# Overgang.net
KiCad netlist of a schematic drawn in EAGLE
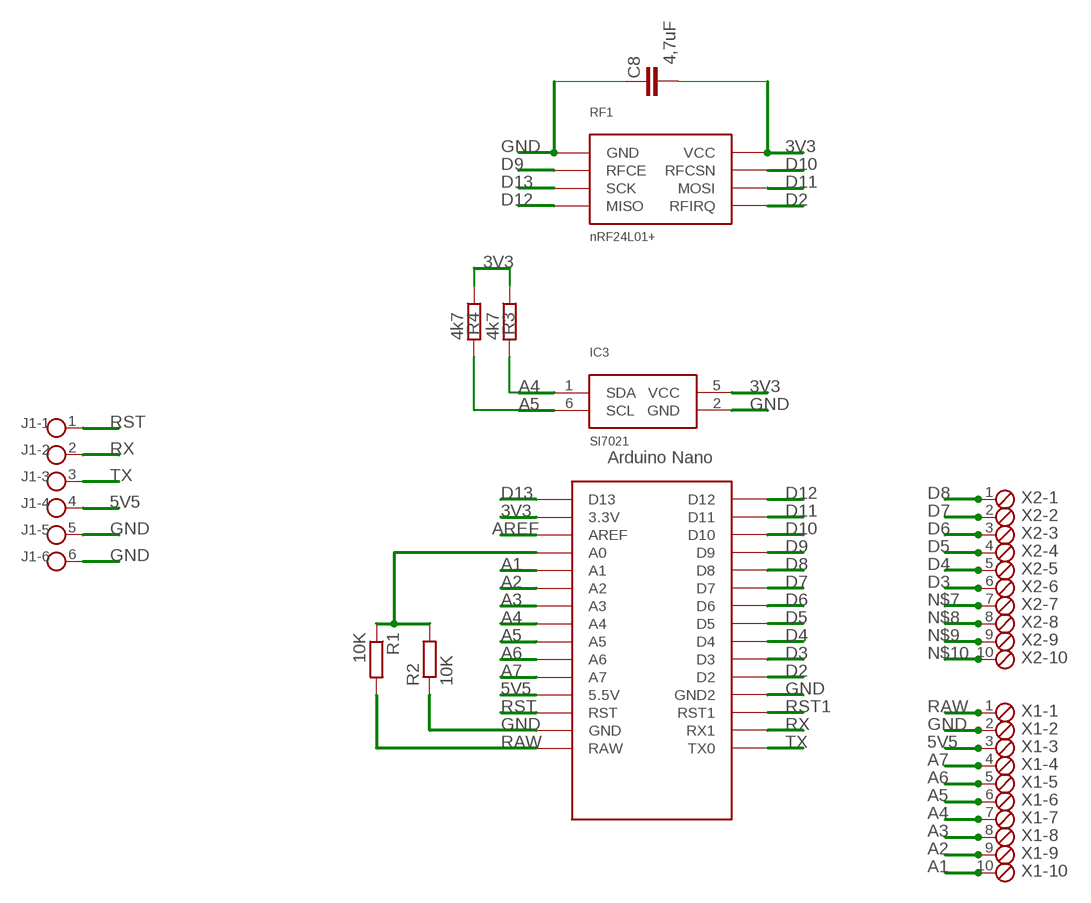
[diagram p0: schematic, sheet 1]

(export (version "E")
  (design (tool "Eeschema 10.0.6"))
  (components
    (comp (ref "C8")
      (value "4,7uF")
      (footprint "eagle-import:C1206K")
      (libsource (lib "eagle-import") (part "C-EUC1206K"))
    )
    (comp (ref "IC3")
      (value "SI7021")
      (footprint "eagle-import:DFN6")
      (libsource (lib "eagle-import") (part "SI7021"))
    )
    (comp (ref "J1")
      (value "FTDI")
      (footprint "eagle-import:LIST6B")
      (libsource (lib "eagle-import") (part "LIST6LIST6B"))
    )
    (comp (ref "R1")
      (value "10K")
      (footprint "eagle-import:R0805")
      (libsource (lib "eagle-import") (part "R-EU_R0805"))
    )
    (comp (ref "R2")
      (value "10K")
      (footprint "eagle-import:R0805")
      (libsource (lib "eagle-import") (part "R-EU_R0805"))
    )
    (comp (ref "R3")
      (value "4k7")
      (footprint "eagle-import:R0805")
      (libsource (lib "eagle-import") (part "R-EU_R0805"))
    )
    (comp (ref "R4")
      (value "4k7")
      (footprint "eagle-import:R0805")
      (libsource (lib "eagle-import") (part "R-EU_R0805"))
    )
    (comp (ref "RF1")
      (value "nRF24L01+")
      (footprint "eagle-import:2X4-2.54MM")
      (libsource (lib "eagle-import") (part "NRF24L01"))
    )
    (comp (ref "U$1")
      (value "NANO")
      (footprint "eagle-import:NANO")
      (libsource (lib "eagle-import") (part "NANO"))
    )
    (comp (ref "X1")
      (value "MPT10")
      (footprint "eagle-import:10POL254")
      (libsource (lib "eagle-import") (part "MPT10"))
    )
    (comp (ref "X2")
      (value "MPT10")
      (footprint "eagle-import:10POL254")
      (libsource (lib "eagle-import") (part "MPT10"))
    )
  )
  (nets
    (net (code "1") (name "/3V3") (class "Default")
      (node (ref "C8") (pin "1") (pinfunction "1_1") (pintype "passive"))
      (node (ref "IC3") (pin "5") (pinfunction "VCC_5") (pintype "bidirectional"))
      (node (ref "R3") (pin "1") (pinfunction "1_1") (pintype "passive"))
      (node (ref "R4") (pin "1") (pinfunction "1_1") (pintype "passive"))
      (node (ref "RF1") (pin "P$2") (pinfunction "VCC_P$2") (pintype "power_in"))
      (node (ref "U$1") (pin "3.3V") (pinfunction "3.3V_3.3V") (pintype "bidirectional"))
    )
    (net (code "2") (name "/5V5") (class "Default")
      (node (ref "J1") (pin "4") (pinfunction "1_4") (pintype "passive"))
      (node (ref "U$1") (pin "5V") (pinfunction "5.5V_5V") (pintype "bidirectional"))
      (node (ref "X1") (pin "3") (pinfunction "1_3") (pintype "passive"))
    )
    (net (code "3") (name "/A1") (class "Default")
      (node (ref "U$1") (pin "A1") (pinfunction "A1_A1") (pintype "bidirectional"))
      (node (ref "X1") (pin "10") (pinfunction "1_10") (pintype "passive"))
    )
    (net (code "4") (name "/A2") (class "Default")
      (node (ref "U$1") (pin "A2") (pinfunction "A2_A2") (pintype "bidirectional"))
      (node (ref "X1") (pin "9") (pinfunction "1_9") (pintype "passive"))
    )
    (net (code "5") (name "/A3") (class "Default")
      (node (ref "U$1") (pin "A3") (pinfunction "A3_A3") (pintype "bidirectional"))
      (node (ref "X1") (pin "8") (pinfunction "1_8") (pintype "passive"))
    )
    (net (code "6") (name "/A4") (class "Default")
      (node (ref "IC3") (pin "1") (pinfunction "SDA_1") (pintype "bidirectional"))
      (node (ref "R3") (pin "2") (pinfunction "2_2") (pintype "passive"))
      (node (ref "U$1") (pin "A4") (pinfunction "A4_A4") (pintype "bidirectional"))
      (node (ref "X1") (pin "7") (pinfunction "1_7") (pintype "passive"))
    )
    (net (code "7") (name "/A5") (class "Default")
      (node (ref "IC3") (pin "6") (pinfunction "SCL_6") (pintype "bidirectional"))
      (node (ref "R4") (pin "2") (pinfunction "2_2") (pintype "passive"))
      (node (ref "U$1") (pin "A5") (pinfunction "A5_A5") (pintype "bidirectional"))
      (node (ref "X1") (pin "6") (pinfunction "1_6") (pintype "passive"))
    )
    (net (code "8") (name "/A6") (class "Default")
      (node (ref "U$1") (pin "A6") (pinfunction "A6_A6") (pintype "bidirectional"))
      (node (ref "X1") (pin "5") (pinfunction "1_5") (pintype "passive"))
    )
    (net (code "9") (name "/A7") (class "Default")
      (node (ref "U$1") (pin "A7") (pinfunction "A7_A7") (pintype "bidirectional"))
      (node (ref "X1") (pin "4") (pinfunction "1_4") (pintype "passive"))
    )
    (net (code "10") (name "/AREF") (class "Default")
      (node (ref "U$1") (pin "AREF") (pinfunction "AREF_AREF") (pintype "bidirectional"))
    )
    (net (code "11") (name "/D2") (class "Default")
      (node (ref "RF1") (pin "P$8") (pinfunction "RFIRQ_P$8") (pintype "output"))
      (node (ref "U$1") (pin "D2") (pinfunction "D2_D2") (pintype "bidirectional"))
    )
    (net (code "12") (name "/D3") (class "Default")
      (node (ref "U$1") (pin "D3") (pinfunction "D3_D3") (pintype "bidirectional"))
      (node (ref "X2") (pin "6") (pinfunction "1_6") (pintype "passive"))
    )
    (net (code "13") (name "/D4") (class "Default")
      (node (ref "U$1") (pin "D4") (pinfunction "D4_D4") (pintype "bidirectional"))
      (node (ref "X2") (pin "5") (pinfunction "1_5") (pintype "passive"))
    )
    (net (code "14") (name "/D5") (class "Default")
      (node (ref "U$1") (pin "D5") (pinfunction "D5_D5") (pintype "bidirectional"))
      (node (ref "X2") (pin "4") (pinfunction "1_4") (pintype "passive"))
    )
    (net (code "15") (name "/D6") (class "Default")
      (node (ref "U$1") (pin "D6") (pinfunction "D6_D6") (pintype "bidirectional"))
      (node (ref "X2") (pin "3") (pinfunction "1_3") (pintype "passive"))
    )
    (net (code "16") (name "/D7") (class "Default")
      (node (ref "U$1") (pin "D7") (pinfunction "D7_D7") (pintype "bidirectional"))
      (node (ref "X2") (pin "2") (pinfunction "1_2") (pintype "passive"))
    )
    (net (code "17") (name "/D8") (class "Default")
      (node (ref "U$1") (pin "D8") (pinfunction "D8_D8") (pintype "bidirectional"))
      (node (ref "X2") (pin "1") (pinfunction "1_1") (pintype "passive"))
    )
    (net (code "18") (name "/D9") (class "Default")
      (node (ref "RF1") (pin "P$3") (pinfunction "RFCE_P$3") (pintype "input"))
      (node (ref "U$1") (pin "D9") (pinfunction "D9_D9") (pintype "bidirectional"))
    )
    (net (code "19") (name "/D10") (class "Default")
      (node (ref "RF1") (pin "P$4") (pinfunction "RFCSN_P$4") (pintype "bidirectional"))
      (node (ref "U$1") (pin "D10") (pinfunction "D10_D10") (pintype "bidirectional"))
    )
    (net (code "20") (name "/D11") (class "Default")
      (node (ref "RF1") (pin "P$6") (pinfunction "MOSI_P$6") (pintype "bidirectional"))
      (node (ref "U$1") (pin "D11") (pinfunction "D11_D11") (pintype "bidirectional"))
    )
    (net (code "21") (name "/D12") (class "Default")
      (node (ref "RF1") (pin "P$7") (pinfunction "MISO_P$7") (pintype "bidirectional"))
      (node (ref "U$1") (pin "D12") (pinfunction "D12_D12") (pintype "bidirectional"))
    )
    (net (code "22") (name "/D13") (class "Default")
      (node (ref "RF1") (pin "P$5") (pinfunction "SCK_P$5") (pintype "input"))
      (node (ref "U$1") (pin "D13") (pinfunction "D13_D13") (pintype "bidirectional"))
    )
    (net (code "23") (name "/GND") (class "Default")
      (node (ref "C8") (pin "2") (pinfunction "2_2") (pintype "passive"))
      (node (ref "IC3") (pin "2") (pinfunction "GND_2") (pintype "bidirectional"))
      (node (ref "J1") (pin "5") (pinfunction "1_5") (pintype "passive"))
      (node (ref "J1") (pin "6") (pinfunction "1_6") (pintype "passive"))
      (node (ref "R2") (pin "1") (pinfunction "1_1") (pintype "passive"))
      (node (ref "RF1") (pin "P$1") (pinfunction "GND_P$1") (pintype "power_in"))
      (node (ref "U$1") (pin "GND") (pinfunction "GND_GND") (pintype "bidirectional"))
      (node (ref "U$1") (pin "GND1") (pinfunction "GND2_GND1") (pintype "bidirectional"))
      (node (ref "X1") (pin "2") (pinfunction "1_2") (pintype "passive"))
    )
    (net (code "24") (name "/N$7") (class "Default")
      (node (ref "X2") (pin "7") (pinfunction "1_7") (pintype "passive"))
    )
    (net (code "25") (name "/N$8") (class "Default")
      (node (ref "X2") (pin "8") (pinfunction "1_8") (pintype "passive"))
    )
    (net (code "26") (name "/N$9") (class "Default")
      (node (ref "X2") (pin "9") (pinfunction "1_9") (pintype "passive"))
    )
    (net (code "27") (name "/N$10") (class "Default")
      (node (ref "X2") (pin "10") (pinfunction "1_10") (pintype "passive"))
    )
    (net (code "28") (name "/RAW") (class "Default")
      (node (ref "R1") (pin "2") (pinfunction "2_2") (pintype "passive"))
      (node (ref "U$1") (pin "RAW") (pinfunction "RAW_RAW") (pintype "bidirectional"))
      (node (ref "X1") (pin "1") (pinfunction "1_1") (pintype "passive"))
    )
    (net (code "29") (name "/RST") (class "Default")
      (node (ref "J1") (pin "1") (pinfunction "1_1") (pintype "passive"))
      (node (ref "U$1") (pin "RST") (pinfunction "RST_RST") (pintype "bidirectional"))
    )
    (net (code "30") (name "/RST1") (class "Default")
      (node (ref "U$1") (pin "RST1") (pinfunction "RST1_RST1") (pintype "bidirectional"))
    )
    (net (code "31") (name "/RX") (class "Default")
      (node (ref "J1") (pin "2") (pinfunction "1_2") (pintype "passive"))
      (node (ref "U$1") (pin "RX1") (pinfunction "RX1_RX1") (pintype "bidirectional"))
    )
    (net (code "32") (name "/TX") (class "Default")
      (node (ref "J1") (pin "3") (pinfunction "1_3") (pintype "passive"))
      (node (ref "U$1") (pin "TX0") (pinfunction "TX0_TX0") (pintype "bidirectional"))
    )
    (net (code "33") (name "Net-(R1-Pad1)") (class "Default")
      (node (ref "R1") (pin "1") (pinfunction "1_1") (pintype "passive"))
      (node (ref "R2") (pin "2") (pinfunction "2_2") (pintype "passive"))
      (node (ref "U$1") (pin "A0") (pinfunction "A0_A0") (pintype "bidirectional"))
    )
    (net (code "34") (name "unconnected-(U$1-PadICSP1)") (class "Default")
      (node (ref "U$1") (pin "ICSP1") (pinfunction "ICSP1_ICSP1") (pintype "bidirectional"))
    )
    (net (code "35") (name "unconnected-(U$1-PadICSP2)") (class "Default")
      (node (ref "U$1") (pin "ICSP2") (pinfunction "ICSP2_ICSP2") (pintype "bidirectional"))
    )
    (net (code "36") (name "unconnected-(U$1-PadICSP3)") (class "Default")
      (node (ref "U$1") (pin "ICSP3") (pinfunction "ICSP3_ICSP3") (pintype "bidirectional"))
    )
    (net (code "37") (name "unconnected-(U$1-PadICSP4)") (class "Default")
      (node (ref "U$1") (pin "ICSP4") (pinfunction "ICSP4_ICSP4") (pintype "bidirectional"))
    )
    (net (code "38") (name "unconnected-(U$1-PadICSP5)") (class "Default")
      (node (ref "U$1") (pin "ICSP5") (pinfunction "ICSP5_ICSP5") (pintype "bidirectional"))
    )
    (net (code "39") (name "unconnected-(U$1-PadICSP6)") (class "Default")
      (node (ref "U$1") (pin "ICSP6") (pinfunction "ICSP6_ICSP6") (pintype "bidirectional"))
    )
  )
)
